# SD.net
KiCad netlist of a schematic drawn in Altium Designer
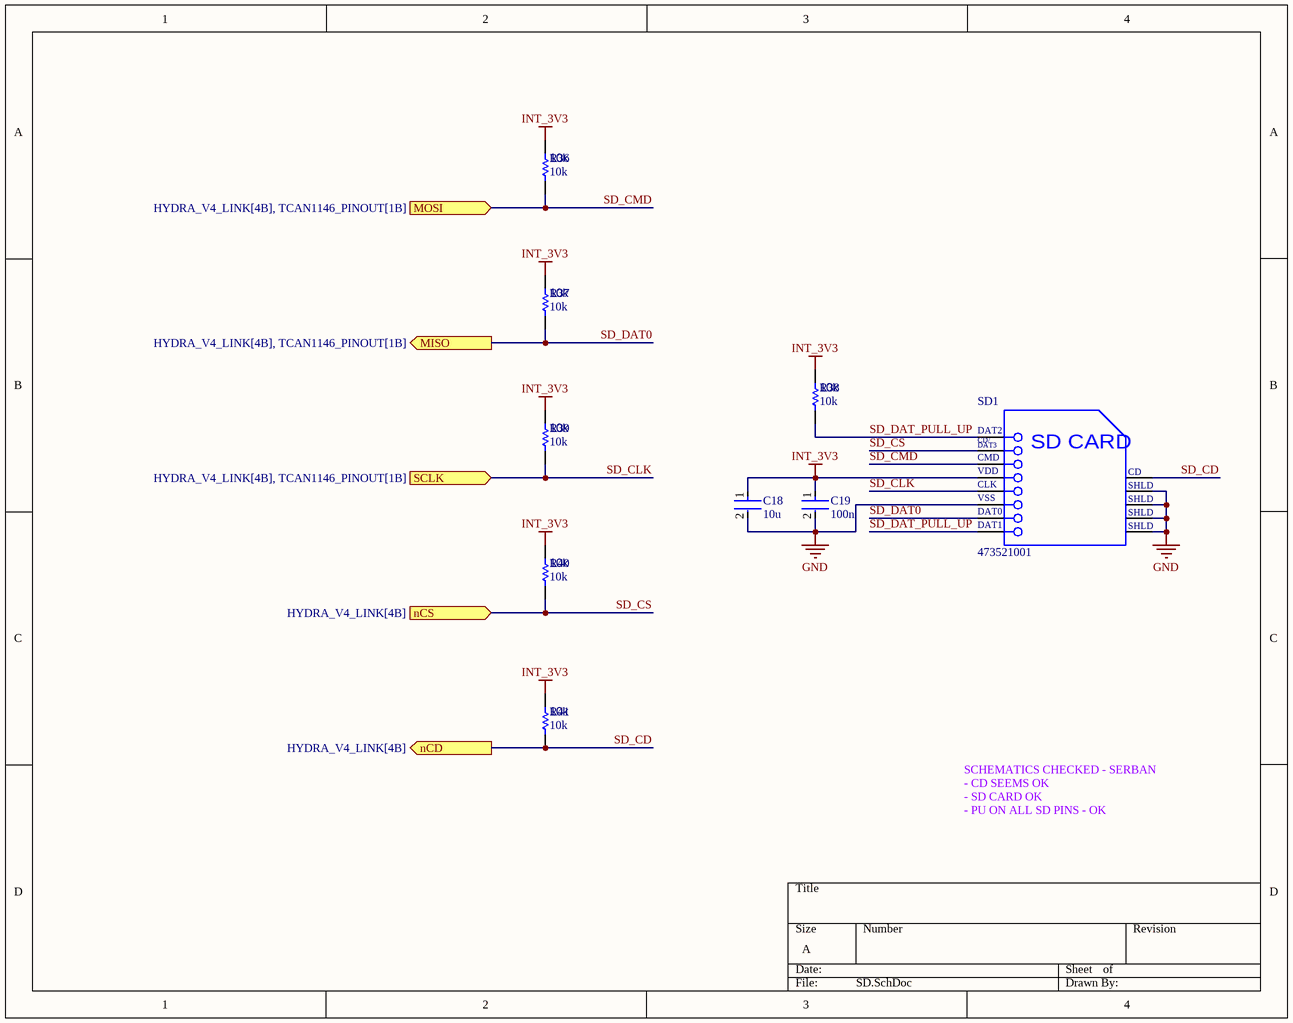
[diagram p0: SD.SchDoc]

(export (version "E")
  (design (tool "Eeschema 10.0.6"))
  (components
    (comp (ref "C18")
      (value "10u")
      (footprint "FP-0402-L_1_0_0_05-W_0_5-IPC_A")
      (description "LARGE PADS, 0402 CAP, CHANGE COMMENT TO MATCH REAL P/N")
      (libsource (lib "Space Concordia") (part "b4654b650e69147ec39a6b967a45e02"))
    )
    (comp (ref "C19")
      (value "100n")
      (footprint "FP-0402-L_1_0_0_05-W_0_5-IPC_A")
      (description "LARGE PADS, 0402 CAP, CHANGE COMMENT TO MATCH REAL P/N")
      (libsource (lib "Space Concordia") (part "b4654b650e69147ec39a6b967a45e02"))
    )
    (comp (ref "R36")
      (value "10k")
      (footprint "R0603B")
      (description "Resistor")
      (fields (field (name "ALTIUM_VALUE") "10k"))
      (libsource (lib "Space Concordia") (part "Resistor"))
    )
    (comp (ref "R37")
      (value "10k")
      (footprint "R0603B")
      (description "Resistor")
      (fields (field (name "ALTIUM_VALUE") "10k"))
      (libsource (lib "Space Concordia") (part "Resistor"))
    )
    (comp (ref "R38")
      (value "10k")
      (footprint "R0603B")
      (description "Resistor")
      (fields (field (name "ALTIUM_VALUE") "10k"))
      (libsource (lib "Space Concordia") (part "Resistor"))
    )
    (comp (ref "R39")
      (value "10k")
      (footprint "R0603B")
      (description "Resistor")
      (fields (field (name "ALTIUM_VALUE") "10k"))
      (libsource (lib "Space Concordia") (part "Resistor"))
    )
    (comp (ref "R40")
      (value "10k")
      (footprint "R0603B")
      (description "Resistor")
      (fields (field (name "ALTIUM_VALUE") "10k"))
      (libsource (lib "Space Concordia") (part "Resistor"))
    )
    (comp (ref "R41")
      (value "10k")
      (footprint "R0603B")
      (description "Resistor")
      (fields (field (name "ALTIUM_VALUE") "10k"))
      (libsource (lib "Space Concordia") (part "Resistor"))
    )
    (comp (ref "SD1")
      (value "473521001")
      (footprint "MOLX-473521001_V")
      (description "MicroSD(TM), Pitch 1.1 mm, 8 Position, Height 1.88 mm, -20 to 85 degC, RoHS, Tape and Reel")
      (fields (field (name "MANUFACTURER") "Molex"))
      (libsource (lib "Altium Content Vault") (part "CN-SD-8-1SW-4S"))
    )
  )
  (nets
    (net (code "1") (name "/SD_CD") (class "Default")
      (node (ref "R41") (pin "2") (pinfunction "2_2") (pintype "passive"))
      (node (ref "SD1") (pin "9") (pinfunction "CD_9") (pintype "passive"))
    )
    (net (code "2") (name "/SD_CLK") (class "Default")
      (node (ref "R39") (pin "2") (pinfunction "2_2") (pintype "passive"))
      (node (ref "SD1") (pin "5") (pinfunction "CLK_5") (pintype "passive"))
    )
    (net (code "3") (name "/SD_CMD") (class "Default")
      (node (ref "R36") (pin "2") (pinfunction "2_2") (pintype "passive"))
      (node (ref "SD1") (pin "3") (pinfunction "CMD_3") (pintype "passive"))
    )
    (net (code "4") (name "/SD_CS") (class "Default")
      (node (ref "R40") (pin "2") (pinfunction "2_2") (pintype "passive"))
      (node (ref "SD1") (pin "2") (pinfunction "CD/DAT3_2") (pintype "passive"))
    )
    (net (code "5") (name "/SD_DAT0") (class "Default")
      (node (ref "R37") (pin "2") (pinfunction "2_2") (pintype "passive"))
      (node (ref "SD1") (pin "7") (pinfunction "DAT0_7") (pintype "passive"))
    )
    (net (code "6") (name "/SD_DAT_PULL_UP") (class "Default")
      (node (ref "R38") (pin "2") (pinfunction "2_2") (pintype "passive"))
      (node (ref "SD1") (pin "1") (pinfunction "DAT2_1") (pintype "passive"))
      (node (ref "SD1") (pin "8") (pinfunction "DAT1_8") (pintype "passive"))
    )
    (net (code "7") (name "GND") (class "Default")
      (node (ref "C18") (pin "2") (pinfunction "2_2") (pintype "passive"))
      (node (ref "C19") (pin "2") (pinfunction "2_2") (pintype "passive"))
      (node (ref "SD1") (pin "10") (pinfunction "SHLD_10") (pintype "passive"))
      (node (ref "SD1") (pin "11") (pinfunction "SHLD_11") (pintype "passive"))
      (node (ref "SD1") (pin "12") (pinfunction "SHLD_12") (pintype "passive"))
      (node (ref "SD1") (pin "13") (pinfunction "SHLD_13") (pintype "passive"))
      (node (ref "SD1") (pin "6") (pinfunction "VSS_6") (pintype "passive"))
    )
    (net (code "8") (name "INT_3V3") (class "Default")
      (node (ref "C18") (pin "1") (pinfunction "1_1") (pintype "passive"))
      (node (ref "C19") (pin "1") (pinfunction "1_1") (pintype "passive"))
      (node (ref "R36") (pin "1") (pinfunction "1_1") (pintype "passive"))
      (node (ref "R37") (pin "1") (pinfunction "1_1") (pintype "passive"))
      (node (ref "R38") (pin "1") (pinfunction "1_1") (pintype "passive"))
      (node (ref "R39") (pin "1") (pinfunction "1_1") (pintype "passive"))
      (node (ref "R40") (pin "1") (pinfunction "1_1") (pintype "passive"))
      (node (ref "R41") (pin "1") (pinfunction "1_1") (pintype "passive"))
      (node (ref "SD1") (pin "4") (pinfunction "VDD_4") (pintype "passive"))
    )
  )
)
